# Current_Sensor.net
KiCad netlist of a schematic drawn in Altium Designer
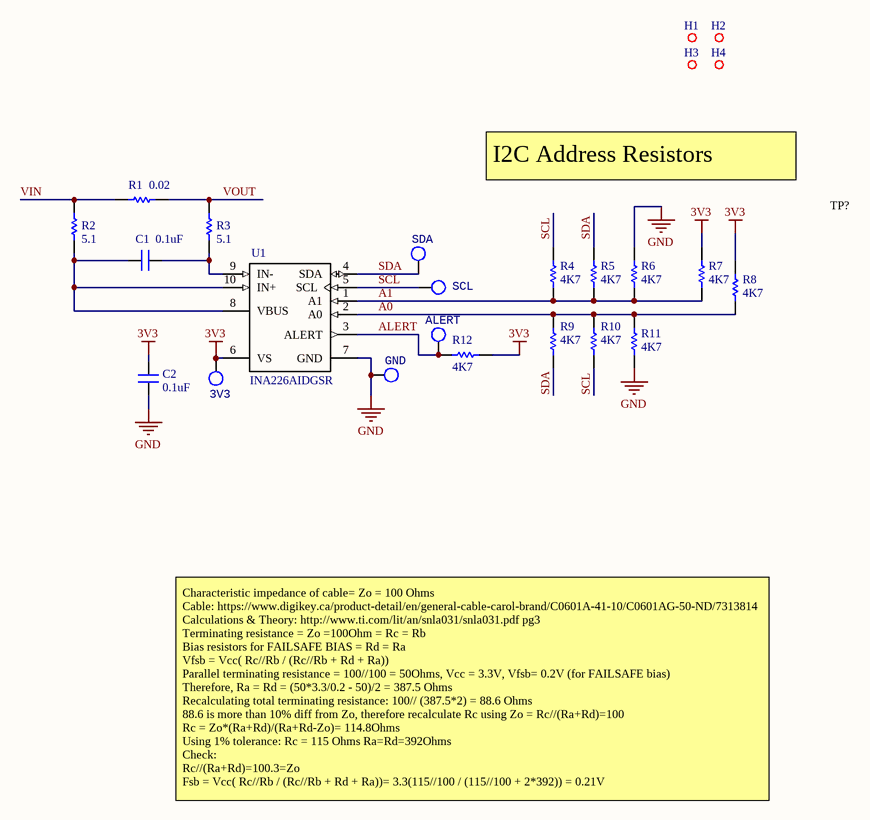
[diagram p0: Current Sensor.SchDoc]

(export (version "E")
  (design (tool "Eeschema 10.0.6"))
  (components
    (comp (ref "C1")
      (value "0.1uF")
      (footprint "CAPC2012X140N")
      (description "CAP CER 0.1UF 50V X7R 0805")
      (fields (field (name "TOLERANCE") "10%") (field (name "Comment") "CAP_0.1uF_50V_0805"))
      (libsource (lib "UWRT_Schematic_Library_2020") (part "CAP_0.1uF_50V_0805"))
    )
    (comp (ref "C2")
      (value "0.1uF")
      (footprint "CAPC2012X140N")
      (description "CAP CER 0.1UF 50V X7R 0805")
      (fields (field (name "TOLERANCE") "10%") (field (name "Comment") "CAP_0.1uF_50V_0805"))
      (libsource (lib "UWRT_Schematic_Library_2020") (part "CAP_0.1uF_50V_0805"))
    )
    (comp (ref "H1")
      (value "MOUNTING_HOLES")
      (footprint "MOUNTING_HOLE")
      (description "6cm x 6cm")
      (libsource (lib "UWRT_Schematic_Library_2020") (part "MOUNTING_HOLES"))
    )
    (comp (ref "H2")
      (value "MOUNTING_HOLES")
      (footprint "MOUNTING_HOLE")
      (description "6cm x 6cm")
      (libsource (lib "UWRT_Schematic_Library_2020") (part "MOUNTING_HOLES"))
    )
    (comp (ref "H3")
      (value "MOUNTING_HOLES")
      (footprint "MOUNTING_HOLE")
      (description "6cm x 6cm")
      (libsource (lib "UWRT_Schematic_Library_2020") (part "MOUNTING_HOLES"))
    )
    (comp (ref "H4")
      (value "MOUNTING_HOLES")
      (footprint "MOUNTING_HOLE")
      (description "6cm x 6cm")
      (libsource (lib "UWRT_Schematic_Library_2020") (part "MOUNTING_HOLES"))
    )
    (comp (ref "R1")
      (value "0.02")
      (footprint "RESC6532X75N")
      (description "RES 0.02 OHM 1% 3W 2512")
      (fields (field (name "Comment") "RES_20m_2512"))
      (libsource (lib "UWRT_Schematic_Library_2020") (part "RES_20m_2512"))
    )
    (comp (ref "R2")
      (value "5.1")
      (footprint "RESC2013X70X40LL20T20")
      (description "RES SMD 5.1 OHM 5% 1/8W 0805")
      (fields (field (name "PART NUMBER") "ERJ-6GEYJ5R1V") (field (name "MANUFACTURER") "Panasonic"))
      (libsource (lib "UWRT_Schematic_Library_2020") (part "RES_5.1_0805"))
    )
    (comp (ref "R3")
      (value "5.1")
      (footprint "RESC2013X70X40LL20T20")
      (description "RES SMD 5.1 OHM 5% 1/8W 0805")
      (fields (field (name "PART NUMBER") "ERJ-6GEYJ5R1V") (field (name "MANUFACTURER") "Panasonic"))
      (libsource (lib "UWRT_Schematic_Library_2020") (part "RES_5.1_0805"))
    )
    (comp (ref "R4")
      (value "4K7")
      (footprint "RESC2012X60N")
      (description "RES SMD 4.7K OHM 5% 1/8W 0805")
      (fields (field (name "TOLERANCE") "5%") (field (name "Comment") "RES_4K7_0805"))
      (libsource (lib "UWRT_Schematic_Library_2020") (part "RES_4K7_0805"))
    )
    (comp (ref "R5")
      (value "4K7")
      (footprint "RESC2012X60N")
      (description "RES SMD 4.7K OHM 5% 1/8W 0805")
      (fields (field (name "TOLERANCE") "5%") (field (name "Comment") "RES_4K7_0805"))
      (libsource (lib "UWRT_Schematic_Library_2020") (part "RES_4K7_0805"))
    )
    (comp (ref "R6")
      (value "4K7")
      (footprint "RESC2012X60N")
      (description "RES SMD 4.7K OHM 5% 1/8W 0805")
      (fields (field (name "TOLERANCE") "5%") (field (name "Comment") "RES_4K7_0805"))
      (libsource (lib "UWRT_Schematic_Library_2020") (part "RES_4K7_0805"))
    )
    (comp (ref "R7")
      (value "4K7")
      (footprint "RESC2012X60N")
      (description "RES SMD 4.7K OHM 5% 1/8W 0805")
      (fields (field (name "TOLERANCE") "5%") (field (name "Comment") "RES_4K7_0805"))
      (libsource (lib "UWRT_Schematic_Library_2020") (part "RES_4K7_0805"))
    )
    (comp (ref "R8")
      (value "4K7")
      (footprint "RESC2012X60N")
      (description "RES SMD 4.7K OHM 5% 1/8W 0805")
      (fields (field (name "TOLERANCE") "5%") (field (name "Comment") "RES_4K7_0805"))
      (libsource (lib "UWRT_Schematic_Library_2020") (part "RES_4K7_0805"))
    )
    (comp (ref "R9")
      (value "4K7")
      (footprint "RESC2012X60N")
      (description "RES SMD 4.7K OHM 5% 1/8W 0805")
      (fields (field (name "TOLERANCE") "5%") (field (name "Comment") "RES_4K7_0805"))
      (libsource (lib "UWRT_Schematic_Library_2020") (part "RES_4K7_0805"))
    )
    (comp (ref "R10")
      (value "4K7")
      (footprint "RESC2012X60N")
      (description "RES SMD 4.7K OHM 5% 1/8W 0805")
      (fields (field (name "TOLERANCE") "5%") (field (name "Comment") "RES_4K7_0805"))
      (libsource (lib "UWRT_Schematic_Library_2020") (part "RES_4K7_0805"))
    )
    (comp (ref "R11")
      (value "4K7")
      (footprint "RESC2012X60N")
      (description "RES SMD 4.7K OHM 5% 1/8W 0805")
      (fields (field (name "TOLERANCE") "5%") (field (name "Comment") "RES_4K7_0805"))
      (libsource (lib "UWRT_Schematic_Library_2020") (part "RES_4K7_0805"))
    )
    (comp (ref "R12")
      (value "4K7")
      (footprint "RESC2012X60N")
      (description "RES SMD 4.7K OHM 5% 1/8W 0805")
      (fields (field (name "TOLERANCE") "5%") (field (name "Comment") "RES_4K7_0805"))
      (libsource (lib "UWRT_Schematic_Library_2020") (part "RES_4K7_0805"))
    )
    (comp (ref "TP3")
      (value "SDA")
      (footprint "TESTPOINT_LOOP")
      (description "Loop testpoint through-hole pad")
      (fields (field (name "MANUFACTURER") "Keystone Electronics"))
      (libsource (lib "UWRT_Schematic_Library_2020") (part "TESTPOINT_LOOP"))
    )
    (comp (ref "TP5")
      (value "SCL")
      (footprint "TESTPOINT_LOOP")
      (description "Loop testpoint through-hole pad")
      (fields (field (name "MANUFACTURER") "Keystone Electronics"))
      (libsource (lib "UWRT_Schematic_Library_2020") (part "TESTPOINT_LOOP"))
    )
    (comp (ref "TP7")
      (value "ALERT")
      (footprint "TESTPOINT_LOOP")
      (description "Loop testpoint through-hole pad")
      (fields (field (name "MANUFACTURER") "Keystone Electronics"))
      (libsource (lib "UWRT_Schematic_Library_2020") (part "TESTPOINT_LOOP"))
    )
    (comp (ref "TP8")
      (value "GND")
      (footprint "TESTPOINT_LOOP")
      (description "Loop testpoint through-hole pad")
      (fields (field (name "MANUFACTURER") "Keystone Electronics"))
      (libsource (lib "UWRT_Schematic_Library_2020") (part "TESTPOINT_LOOP"))
    )
    (comp (ref "TP9")
      (value "3V3")
      (footprint "TESTPOINT_LOOP")
      (description "Loop testpoint through-hole pad")
      (fields (field (name "MANUFACTURER") "Keystone Electronics"))
      (libsource (lib "UWRT_Schematic_Library_2020") (part "TESTPOINT_LOOP"))
    )
    (comp (ref "U1")
      (value "INA226AIDGSR")
      (footprint "INA226AIDGSR")
      (description "IC MONITOR PWR/CURR BIDIR 10MSOP")
      (fields (field (name "MF") "Texas Instruments"))
      (libsource (lib "UWRT_Schematic_Library_2020") (part "INA226AIDGSR"))
    )
  )
  (nets
    (net (code "1") (name "/A0") (class "Default")
      (node (ref "R10") (pin "1") (pinfunction "1_1") (pintype "passive"))
      (node (ref "R11") (pin "1") (pinfunction "1_1") (pintype "passive"))
      (node (ref "R8") (pin "1") (pinfunction "1_1") (pintype "passive"))
      (node (ref "R9") (pin "1") (pinfunction "1_1") (pintype "passive"))
      (node (ref "U1") (pin "2") (pinfunction "A0_2") (pintype "input"))
    )
    (net (code "2") (name "/A1") (class "Default")
      (node (ref "R4") (pin "1") (pinfunction "1_1") (pintype "passive"))
      (node (ref "R5") (pin "1") (pinfunction "1_1") (pintype "passive"))
      (node (ref "R6") (pin "1") (pinfunction "1_1") (pintype "passive"))
      (node (ref "R7") (pin "1") (pinfunction "1_1") (pintype "passive"))
      (node (ref "U1") (pin "1") (pinfunction "A1_1") (pintype "input"))
    )
    (net (code "3") (name "/ALERT") (class "Default")
      (node (ref "R12") (pin "1") (pinfunction "1_1") (pintype "passive"))
      (node (ref "TP7") (pin "1") (pintype "passive"))
      (node (ref "U1") (pin "3") (pinfunction "ALERT_3") (pintype "output"))
    )
    (net (code "4") (name "/SCL") (class "Default")
      (node (ref "R10") (pin "2") (pinfunction "2_2") (pintype "passive"))
      (node (ref "R4") (pin "2") (pinfunction "2_2") (pintype "passive"))
      (node (ref "TP5") (pin "1") (pintype "passive"))
      (node (ref "U1") (pin "5") (pinfunction "SCL_5") (pintype "input"))
    )
    (net (code "5") (name "/SDA") (class "Default")
      (node (ref "R5") (pin "2") (pinfunction "2_2") (pintype "passive"))
      (node (ref "R9") (pin "2") (pinfunction "2_2") (pintype "passive"))
      (node (ref "TP3") (pin "1") (pintype "passive"))
      (node (ref "U1") (pin "4") (pinfunction "SDA_4") (pintype "bidirectional"))
    )
    (net (code "6") (name "/VIN") (class "Default")
      (node (ref "R1") (pin "1") (pinfunction "1_1") (pintype "passive"))
      (node (ref "R2") (pin "2") (pinfunction "2_2") (pintype "passive"))
    )
    (net (code "7") (name "/VOUT") (class "Default")
      (node (ref "R1") (pin "2") (pinfunction "2_2") (pintype "passive"))
      (node (ref "R3") (pin "2") (pinfunction "2_2") (pintype "passive"))
    )
    (net (code "8") (name "3V3") (class "Default")
      (node (ref "C2") (pin "2") (pinfunction "2_2") (pintype "passive"))
      (node (ref "R12") (pin "2") (pinfunction "2_2") (pintype "passive"))
      (node (ref "R7") (pin "2") (pinfunction "2_2") (pintype "passive"))
      (node (ref "R8") (pin "2") (pinfunction "2_2") (pintype "passive"))
      (node (ref "TP9") (pin "1") (pintype "passive"))
      (node (ref "U1") (pin "6") (pinfunction "VS_6") (pintype "power_in"))
    )
    (net (code "9") (name "GND") (class "Default")
      (node (ref "C2") (pin "1") (pinfunction "1_1") (pintype "passive"))
      (node (ref "R11") (pin "2") (pinfunction "2_2") (pintype "passive"))
      (node (ref "R6") (pin "2") (pinfunction "2_2") (pintype "passive"))
      (node (ref "TP8") (pin "1") (pintype "passive"))
      (node (ref "U1") (pin "7") (pinfunction "GND_7") (pintype "power_in"))
    )
    (net (code "10") (name "Net-(U1-IN+)") (class "Default")
      (node (ref "C1") (pin "1") (pinfunction "1_1") (pintype "passive"))
      (node (ref "R2") (pin "1") (pinfunction "1_1") (pintype "passive"))
      (node (ref "U1") (pin "10") (pinfunction "IN+_10") (pintype "input"))
      (node (ref "U1") (pin "8") (pinfunction "VBUS_8") (pintype "power_in"))
    )
    (net (code "11") (name "Net-(U1-IN-)") (class "Default")
      (node (ref "C1") (pin "2") (pinfunction "2_2") (pintype "passive"))
      (node (ref "R3") (pin "1") (pinfunction "1_1") (pintype "passive"))
      (node (ref "U1") (pin "9") (pinfunction "IN-_9") (pintype "input"))
    )
  )
)
